# Desk_Widget.net
KiCad netlist of a schematic drawn in EAGLE
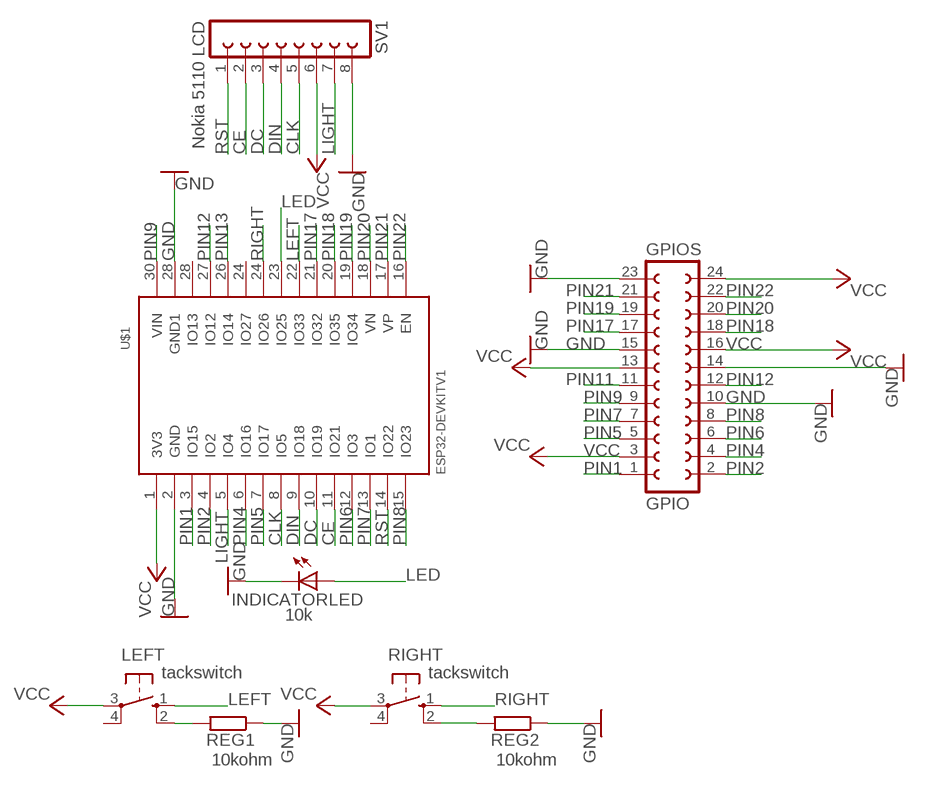
[diagram p0: schematic, sheet 1]

(export (version "E")
  (design (tool "Eeschema 10.0.6"))
  (components
    (comp (ref "GPIOS")
      (value "GPIO")
      (footprint "eagle-import:FE12-2W")
      (libsource (lib "eagle-import") (part "FE12-2W"))
    )
    (comp (ref "INDICATORLED")
      (value "10k")
      (footprint "eagle-import:LED3MM")
      (libsource (lib "eagle-import") (part "LED3MM"))
    )
    (comp (ref "LEFT")
      (value "tackswitch")
      (footprint "eagle-import:B3F-10XX")
      (libsource (lib "eagle-import") (part "10-XX"))
    )
    (comp (ref "REG1")
      (value "10kohm")
      (footprint "eagle-import:0204_7")
      (libsource (lib "eagle-import") (part "R-EU_0204/7"))
    )
    (comp (ref "REG2")
      (value "10kohm")
      (footprint "eagle-import:0204_7")
      (libsource (lib "eagle-import") (part "R-EU_0204/7"))
    )
    (comp (ref "RIGHT")
      (value "tackswitch")
      (footprint "eagle-import:B3F-10XX")
      (libsource (lib "eagle-import") (part "10-XX"))
    )
    (comp (ref "SV1")
      (value "Nokia 5110 LCD")
      (footprint "eagle-import:FE08")
      (libsource (lib "eagle-import") (part "FE08-1"))
    )
    (comp (ref "U$1")
      (value "ESP32DEVKITV1")
      (footprint "eagle-import:ESP32-DEVKITV1")
      (libsource (lib "eagle-import") (part "ESP32DEVKITV1"))
    )
  )
  (nets
    (net (code "1") (name "/CE") (class "Default")
      (node (ref "SV1") (pin "2") (pinfunction "2_2") (pintype "passive"))
      (node (ref "U$1") (pin "11") (pinfunction "IO21_11") (pintype "bidirectional"))
    )
    (net (code "2") (name "/CLK") (class "Default")
      (node (ref "SV1") (pin "5") (pinfunction "5_5") (pintype "passive"))
      (node (ref "U$1") (pin "8") (pinfunction "IO5_8") (pintype "bidirectional"))
    )
    (net (code "3") (name "/DC") (class "Default")
      (node (ref "SV1") (pin "3") (pinfunction "3_3") (pintype "passive"))
      (node (ref "U$1") (pin "10") (pinfunction "IO19_10") (pintype "bidirectional"))
    )
    (net (code "4") (name "/DIN") (class "Default")
      (node (ref "SV1") (pin "4") (pinfunction "4_4") (pintype "passive"))
      (node (ref "U$1") (pin "9") (pinfunction "IO18_9") (pintype "bidirectional"))
    )
    (net (code "5") (name "/LED") (class "Default")
      (node (ref "INDICATORLED") (pin "A") (pinfunction "A_A") (pintype "passive"))
      (node (ref "U$1") (pin "23") (pinfunction "IO25_23") (pintype "bidirectional"))
    )
    (net (code "6") (name "/LEFT") (class "Default")
      (node (ref "LEFT") (pin "1") (pinfunction "S_1") (pintype "passive"))
      (node (ref "U$1") (pin "22") (pinfunction "IO33_22") (pintype "bidirectional"))
    )
    (net (code "7") (name "/LIGHT") (class "Default")
      (node (ref "SV1") (pin "7") (pinfunction "7_7") (pintype "passive"))
      (node (ref "U$1") (pin "5") (pinfunction "IO4_5") (pintype "bidirectional"))
    )
    (net (code "8") (name "/PIN1") (class "Default")
      (node (ref "GPIOS") (pin "1") (pinfunction "1_1") (pintype "passive"))
      (node (ref "U$1") (pin "3") (pinfunction "IO15_3") (pintype "bidirectional"))
    )
    (net (code "9") (name "/PIN2") (class "Default")
      (node (ref "GPIOS") (pin "2") (pinfunction "2_2") (pintype "passive"))
      (node (ref "U$1") (pin "4") (pinfunction "IO2_4") (pintype "bidirectional"))
    )
    (net (code "10") (name "/PIN4") (class "Default")
      (node (ref "GPIOS") (pin "4") (pinfunction "4_4") (pintype "passive"))
      (node (ref "U$1") (pin "6") (pinfunction "IO16_6") (pintype "bidirectional"))
    )
    (net (code "11") (name "/PIN5") (class "Default")
      (node (ref "GPIOS") (pin "5") (pinfunction "5_5") (pintype "passive"))
      (node (ref "U$1") (pin "7") (pinfunction "IO17_7") (pintype "bidirectional"))
    )
    (net (code "12") (name "/PIN6") (class "Default")
      (node (ref "GPIOS") (pin "6") (pinfunction "6_6") (pintype "passive"))
      (node (ref "U$1") (pin "12") (pinfunction "IO3_12") (pintype "bidirectional"))
    )
    (net (code "13") (name "/PIN7") (class "Default")
      (node (ref "GPIOS") (pin "7") (pinfunction "7_7") (pintype "passive"))
      (node (ref "U$1") (pin "13") (pinfunction "IO1_13") (pintype "bidirectional"))
    )
    (net (code "14") (name "/PIN8") (class "Default")
      (node (ref "GPIOS") (pin "8") (pinfunction "8_8") (pintype "passive"))
      (node (ref "U$1") (pin "15") (pinfunction "IO23_15") (pintype "bidirectional"))
    )
    (net (code "15") (name "/PIN9") (class "Default")
      (node (ref "GPIOS") (pin "9") (pinfunction "9_9") (pintype "passive"))
      (node (ref "U$1") (pin "30") (pinfunction "VIN_30") (pintype "bidirectional"))
    )
    (net (code "16") (name "/PIN11") (class "Default")
      (node (ref "GPIOS") (pin "11") (pinfunction "11_11") (pintype "passive"))
    )
    (net (code "17") (name "/PIN12") (class "Default")
      (node (ref "GPIOS") (pin "12") (pinfunction "12_12") (pintype "passive"))
      (node (ref "U$1") (pin "27") (pinfunction "IO12_27") (pintype "bidirectional"))
    )
    (net (code "18") (name "/PIN13") (class "Default")
      (node (ref "U$1") (pin "26") (pinfunction "IO14_26") (pintype "bidirectional"))
    )
    (net (code "19") (name "/PIN17") (class "Default")
      (node (ref "GPIOS") (pin "17") (pinfunction "17_17") (pintype "passive"))
      (node (ref "U$1") (pin "21") (pinfunction "IO32_21") (pintype "bidirectional"))
    )
    (net (code "20") (name "/PIN18") (class "Default")
      (node (ref "GPIOS") (pin "18") (pinfunction "18_18") (pintype "passive"))
      (node (ref "U$1") (pin "20") (pinfunction "IO35_20") (pintype "bidirectional"))
    )
    (net (code "21") (name "/PIN19") (class "Default")
      (node (ref "GPIOS") (pin "19") (pinfunction "19_19") (pintype "passive"))
      (node (ref "U$1") (pin "19") (pinfunction "IO34_19") (pintype "bidirectional"))
    )
    (net (code "22") (name "/PIN20") (class "Default")
      (node (ref "GPIOS") (pin "20") (pinfunction "20_20") (pintype "passive"))
      (node (ref "U$1") (pin "18") (pinfunction "VN_18") (pintype "bidirectional"))
    )
    (net (code "23") (name "/PIN21") (class "Default")
      (node (ref "GPIOS") (pin "21") (pinfunction "21_21") (pintype "passive"))
      (node (ref "U$1") (pin "17") (pinfunction "VP_17") (pintype "bidirectional"))
    )
    (net (code "24") (name "/PIN22") (class "Default")
      (node (ref "GPIOS") (pin "22") (pinfunction "22_22") (pintype "passive"))
      (node (ref "U$1") (pin "16") (pinfunction "EN_16") (pintype "bidirectional"))
    )
    (net (code "25") (name "/RIGHT") (class "Default")
      (node (ref "RIGHT") (pin "1") (pinfunction "S_1") (pintype "passive"))
      (node (ref "U$1") (pin "24") (pinfunction "IO26_24") (pintype "bidirectional"))
    )
    (net (code "26") (name "/RST") (class "Default")
      (node (ref "SV1") (pin "1") (pinfunction "1_1") (pintype "passive"))
      (node (ref "U$1") (pin "14") (pinfunction "IO22_14") (pintype "bidirectional"))
    )
    (net (code "27") (name "GND") (class "Default")
      (node (ref "GPIOS") (pin "10") (pinfunction "10_10") (pintype "passive"))
      (node (ref "GPIOS") (pin "14") (pinfunction "14_14") (pintype "passive"))
      (node (ref "GPIOS") (pin "15") (pinfunction "15_15") (pintype "passive"))
      (node (ref "GPIOS") (pin "23") (pinfunction "23_23") (pintype "passive"))
      (node (ref "INDICATORLED") (pin "K") (pinfunction "C_K") (pintype "passive"))
      (node (ref "REG1") (pin "1") (pinfunction "1_1") (pintype "passive"))
      (node (ref "REG2") (pin "1") (pinfunction "1_1") (pintype "passive"))
      (node (ref "SV1") (pin "8") (pinfunction "8_8") (pintype "passive"))
      (node (ref "U$1") (pin "2") (pinfunction "GND_2") (pintype "bidirectional"))
      (node (ref "U$1") (pin "28") (pinfunction "GND1_28") (pintype "bidirectional"))
    )
    (net (code "28") (name "Net-(LEFT-S1)") (class "Default")
      (node (ref "LEFT") (pin "2") (pinfunction "S1_2") (pintype "passive"))
      (node (ref "REG1") (pin "2") (pinfunction "2_2") (pintype "passive"))
    )
    (net (code "29") (name "Net-(RIGHT-S1)") (class "Default")
      (node (ref "REG2") (pin "2") (pinfunction "2_2") (pintype "passive"))
      (node (ref "RIGHT") (pin "2") (pinfunction "S1_2") (pintype "passive"))
    )
    (net (code "30") (name "VCC") (class "Default")
      (node (ref "GPIOS") (pin "13") (pinfunction "13_13") (pintype "passive"))
      (node (ref "GPIOS") (pin "16") (pinfunction "16_16") (pintype "passive"))
      (node (ref "GPIOS") (pin "24") (pinfunction "24_24") (pintype "passive"))
      (node (ref "GPIOS") (pin "3") (pinfunction "3_3") (pintype "passive"))
      (node (ref "LEFT") (pin "3") (pinfunction "P_3") (pintype "passive"))
      (node (ref "RIGHT") (pin "3") (pinfunction "P_3") (pintype "passive"))
      (node (ref "SV1") (pin "6") (pinfunction "6_6") (pintype "passive"))
      (node (ref "U$1") (pin "1") (pinfunction "3V3_1") (pintype "bidirectional"))
    )
    (net (code "31") (name "unconnected-(LEFT-P1-Pad4)") (class "Default")
      (node (ref "LEFT") (pin "4") (pinfunction "P1_4") (pintype "passive"))
    )
    (net (code "32") (name "unconnected-(RIGHT-P1-Pad4)") (class "Default")
      (node (ref "RIGHT") (pin "4") (pinfunction "P1_4") (pintype "passive"))
    )
    (net (code "33") (name "unconnected-(U$1-IO13-Pad28)") (class "Default")
      (node (ref "U$1") (pin "28") (pinfunction "IO13_28") (pintype "bidirectional"))
    )
    (net (code "34") (name "unconnected-(U$1-IO27-Pad24)") (class "Default")
      (node (ref "U$1") (pin "24") (pinfunction "IO27_24") (pintype "bidirectional"))
    )
  )
)
